# CT_Adapter.net
KiCad netlist of a schematic drawn in EAGLE
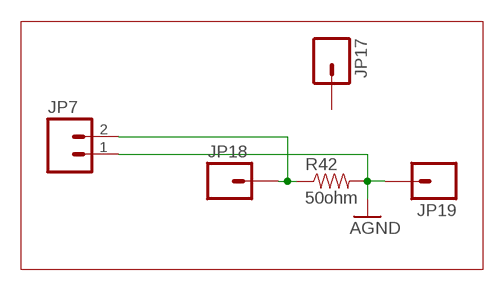
[diagram p0: schematic, sheet 1]

(export (version "E")
  (design (tool "Eeschema 10.0.6"))
  (components
    (comp (ref "JP7")
      (value "M025MM")
      (footprint "eagle-import:SCREWTERMINAL-5MM-2")
      (libsource (lib "eagle-import") (part "M025MM"))
    )
    (comp (ref "JP17")
      (value "M01PTH_LONGPAD")
      (footprint "eagle-import:1X01_LONGPAD")
      (libsource (lib "eagle-import") (part "M01PTH_LONGPAD"))
    )
    (comp (ref "JP18")
      (value "M01PTH_LONGPAD")
      (footprint "eagle-import:1X01_LONGPAD")
      (libsource (lib "eagle-import") (part "M01PTH_LONGPAD"))
    )
    (comp (ref "JP19")
      (value "M01PTH_LONGPAD")
      (footprint "eagle-import:1X01_LONGPAD")
      (libsource (lib "eagle-import") (part "M01PTH_LONGPAD"))
    )
    (comp (ref "R42")
      (value "50ohm")
      (footprint "eagle-import:1206")
      (libsource (lib "eagle-import") (part "RESISTOR1206"))
    )
  )
  (nets
    (net (code "1") (name "AGND") (class "Default")
      (node (ref "JP19") (pin "1") (pinfunction "1_1") (pintype "passive"))
      (node (ref "JP7") (pin "1") (pinfunction "1_1") (pintype "passive"))
      (node (ref "R42") (pin "2") (pinfunction "2_2") (pintype "passive"))
    )
    (net (code "2") (name "Net-(JP18-Pad1)") (class "Default")
      (node (ref "JP18") (pin "1") (pinfunction "1_1") (pintype "passive"))
      (node (ref "JP7") (pin "2") (pinfunction "2_2") (pintype "passive"))
      (node (ref "R42") (pin "1") (pinfunction "1_1") (pintype "passive"))
    )
    (net (code "3") (name "unconnected-(JP17-Pad1)") (class "Default")
      (node (ref "JP17") (pin "1") (pinfunction "1_1") (pintype "passive"))
    )
  )
)
